# Puzzle_Relay_10A_v1_0.net
KiCad netlist of a schematic drawn in EAGLE
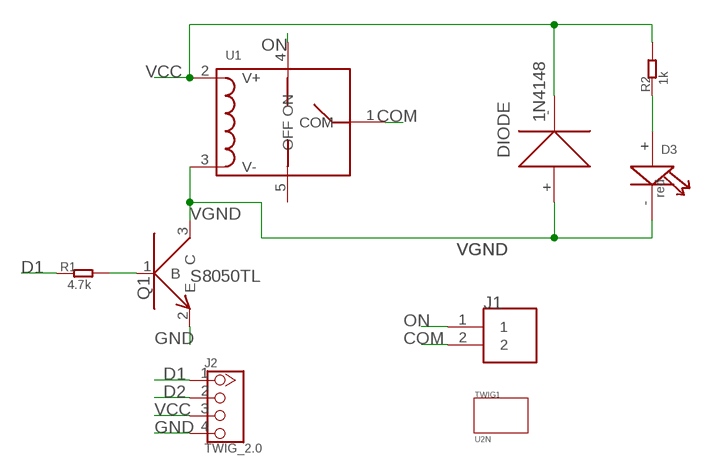
[diagram p0: schematic, sheet 1]

(export (version "E")
  (design (tool "Eeschema 10.0.6"))
  (components
    (comp (ref "D3")
      (value "red")
      (footprint "eagle-import:LED0805")
      (libsource (lib "eagle-import") (part "LED0805"))
    )
    (comp (ref "DIODE")
      (value "1N4148")
      (footprint "eagle-import:DIODE1206")
      (libsource (lib "eagle-import") (part "DIODE1206"))
    )
    (comp (ref "J1")
      (value "CON2")
      (footprint "eagle-import:CON2")
      (libsource (lib "eagle-import") (part "CON2"))
    )
    (comp (ref "J2")
      (value "TWIG_2.0")
      (footprint "eagle-import:2.0_1X4")
      (libsource (lib "eagle-import") (part "TWIG_2.0"))
    )
    (comp (ref "Q1")
      (value "NPN_9013")
      (footprint "eagle-import:SOT23")
      (libsource (lib "eagle-import") (part "NPN_9013"))
    )
    (comp (ref "R1")
      (value "4.7k")
      (footprint "eagle-import:0603")
      (libsource (lib "eagle-import") (part "R0603"))
    )
    (comp (ref "R2")
      (value "1k")
      (footprint "eagle-import:0603")
      (libsource (lib "eagle-import") (part "R0603"))
    )
    (comp (ref "TWIG1")
      (value "U2N")
      (footprint "eagle-import:U2N")
      (libsource (lib "eagle-import") (part "U2N"))
    )
    (comp (ref "U1")
      (value "RELAY")
      (footprint "eagle-import:RELAY")
      (libsource (lib "eagle-import") (part "RELAY"))
    )
  )
  (nets
    (net (code "1") (name "/COM") (class "Default")
      (node (ref "J1") (pin "2") (pinfunction "2_2") (pintype "bidirectional"))
      (node (ref "U1") (pin "1") (pinfunction "COM_1") (pintype "bidirectional"))
    )
    (net (code "2") (name "/D1") (class "Default")
      (node (ref "J2") (pin "1") (pinfunction "1_1") (pintype "bidirectional"))
      (node (ref "R1") (pin "1") (pinfunction "1_1") (pintype "bidirectional"))
    )
    (net (code "3") (name "/D2") (class "Default")
      (node (ref "J2") (pin "2") (pinfunction "2_2") (pintype "bidirectional"))
    )
    (net (code "4") (name "/GND") (class "Default")
      (node (ref "J2") (pin "4") (pinfunction "4_4") (pintype "bidirectional"))
      (node (ref "Q1") (pin "2") (pinfunction "E_2") (pintype "bidirectional"))
    )
    (net (code "5") (name "/ON") (class "Default")
      (node (ref "J1") (pin "1") (pinfunction "1_1") (pintype "bidirectional"))
      (node (ref "U1") (pin "4") (pinfunction "ON_4") (pintype "bidirectional"))
    )
    (net (code "6") (name "/VCC") (class "Default")
      (node (ref "DIODE") (pin "-") (pinfunction "P$2_-") (pintype "bidirectional"))
      (node (ref "J2") (pin "3") (pinfunction "3_3") (pintype "bidirectional"))
      (node (ref "R2") (pin "2") (pinfunction "2_2") (pintype "bidirectional"))
      (node (ref "U1") (pin "2") (pinfunction "V+_2") (pintype "bidirectional"))
    )
    (net (code "7") (name "/VGND") (class "Default")
      (node (ref "D3") (pin "-") (pinfunction "-_-") (pintype "bidirectional"))
      (node (ref "DIODE") (pin "+") (pinfunction "P$1_+") (pintype "bidirectional"))
      (node (ref "Q1") (pin "3") (pinfunction "C_3") (pintype "bidirectional"))
      (node (ref "U1") (pin "3") (pinfunction "V-_3") (pintype "bidirectional"))
    )
    (net (code "8") (name "Net-(D3-Pad+)") (class "Default")
      (node (ref "D3") (pin "+") (pinfunction "+_+") (pintype "bidirectional"))
      (node (ref "R2") (pin "1") (pinfunction "1_1") (pintype "bidirectional"))
    )
    (net (code "9") (name "Net-(Q1-B)") (class "Default")
      (node (ref "Q1") (pin "1") (pinfunction "B_1") (pintype "bidirectional"))
      (node (ref "R1") (pin "2") (pinfunction "2_2") (pintype "bidirectional"))
    )
    (net (code "10") (name "unconnected-(U1-OFF-Pad5)") (class "Default")
      (node (ref "U1") (pin "5") (pinfunction "OFF_5") (pintype "bidirectional"))
    )
  )
)
